# LM13700.net
KiCad netlist of a schematic drawn in EAGLE
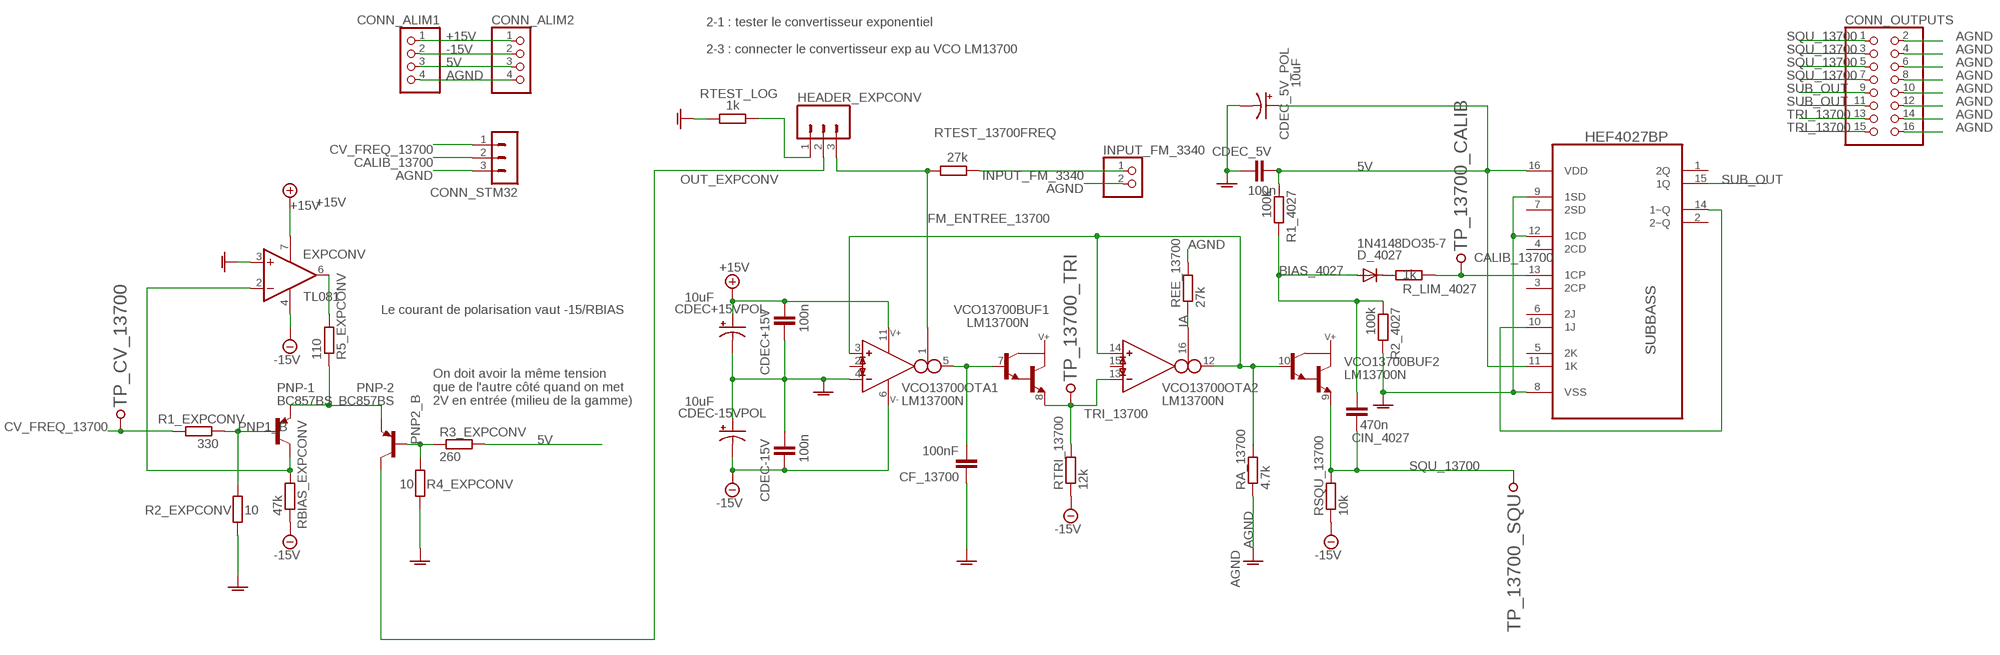
[diagram p0: schematic, sheet 1]

(export (version "E")
  (design (tool "Eeschema 10.0.6"))
  (components
    (comp (ref "CDEC+15V")
      (value "100n")
      (footprint "eagle-import:C025-024X044")
      (libsource (lib "eagle-import") (part "C-EU025-024X044"))
    )
    (comp (ref "CDEC+15VPOL")
      (value "10uF")
      (footprint "eagle-import:CPOL-RADIAL-2.5MM-5MM-KIT")
      (libsource (lib "eagle-import") (part "10UF-POLAR-RADIAL-2.5MM-KIT-25V-20%"))
    )
    (comp (ref "CDEC-15V")
      (value "100n")
      (footprint "eagle-import:C025-024X044")
      (libsource (lib "eagle-import") (part "C-EU025-024X044"))
    )
    (comp (ref "CDEC-15VPOL")
      (value "10uF")
      (footprint "eagle-import:CPOL-RADIAL-2.5MM-5MM-KIT")
      (libsource (lib "eagle-import") (part "10UF-POLAR-RADIAL-2.5MM-KIT-25V-20%"))
    )
    (comp (ref "CDEC_5V")
      (value "100n")
      (footprint "eagle-import:C025-024X044")
      (libsource (lib "eagle-import") (part "C-EU025-024X044"))
    )
    (comp (ref "CDEC_5V_POL")
      (value "10uF")
      (footprint "eagle-import:CPOL-RADIAL-2.5MM-5MM-KIT")
      (libsource (lib "eagle-import") (part "10UF-POLAR-RADIAL-2.5MM-KIT-25V-20%"))
    )
    (comp (ref "CF_13700")
      (value "100nF")
      (footprint "eagle-import:C025-024X044")
      (libsource (lib "eagle-import") (part "C-EU025-024X044"))
    )
    (comp (ref "CIN_4027")
      (value "470n")
      (footprint "eagle-import:C050-024X044")
      (libsource (lib "eagle-import") (part "C-EU050-024X044"))
    )
    (comp (ref "CONN_ALIM1")
      (value "PINHD-1X4")
      (footprint "eagle-import:1X04")
      (libsource (lib "eagle-import") (part "PINHD-1X4"))
    )
    (comp (ref "CONN_ALIM2")
      (value "PINHD-1X4")
      (footprint "eagle-import:1X04")
      (libsource (lib "eagle-import") (part "PINHD-1X4"))
    )
    (comp (ref "CONN_OUTPUTS")
      (value "PINHD-2X8")
      (footprint "eagle-import:2X08")
      (libsource (lib "eagle-import") (part "PINHD-2X8"))
    )
    (comp (ref "CONN_STM32")
      (value "MA03-1")
      (footprint "eagle-import:MA03-1")
      (libsource (lib "eagle-import") (part "MA03-1"))
    )
    (comp (ref "D_4027")
      (value "1N4148DO35-7")
      (footprint "eagle-import:DO35-7")
      (libsource (lib "eagle-import") (part "1N4148DO35-7"))
    )
    (comp (ref "EXPCONV")
      (value "TL081")
      (footprint "eagle-import:DIL08")
      (libsource (lib "eagle-import") (part "1AMP_P7+4N"))
    )
    (comp (ref "HEADER_EXPCONV")
      (value "M03")
      (footprint "eagle-import:03P")
      (libsource (lib "eagle-import") (part "M03"))
    )
    (comp (ref "INPUT_FM_3340")
      (value "PINHD-1X2")
      (footprint "eagle-import:1X02")
      (libsource (lib "eagle-import") (part "PINHD-1X2"))
    )
    (comp (ref "PNP")
      (value "BC857BS")
      (footprint "eagle-import:SOT363")
      (libsource (lib "eagle-import") (part "BC857BS"))
    )
    (comp (ref "R1_4027")
      (value "100k")
      (footprint "eagle-import:0204_5")
      (libsource (lib "eagle-import") (part "R-EU_0204/5"))
    )
    (comp (ref "R1_EXPCONV")
      (value "330")
      (footprint "eagle-import:0204_5")
      (libsource (lib "eagle-import") (part "R-EU_0204/5"))
    )
    (comp (ref "R2_4027")
      (value "100k")
      (footprint "eagle-import:0204_5")
      (libsource (lib "eagle-import") (part "R-EU_0204/5"))
    )
    (comp (ref "R2_EXPCONV")
      (value "10")
      (footprint "eagle-import:0204_5")
      (libsource (lib "eagle-import") (part "R-EU_0204/5"))
    )
    (comp (ref "R3_EXPCONV")
      (value "260")
      (footprint "eagle-import:0204_5")
      (libsource (lib "eagle-import") (part "R-EU_0204/5"))
    )
    (comp (ref "R4_EXPCONV")
      (value "10")
      (footprint "eagle-import:0204_5")
      (libsource (lib "eagle-import") (part "R-EU_0204/5"))
    )
    (comp (ref "R5_EXPCONV")
      (value "110")
      (footprint "eagle-import:0204_5")
      (libsource (lib "eagle-import") (part "R-EU_0204/5"))
    )
    (comp (ref "RA_13700")
      (value "4.7k")
      (footprint "eagle-import:0204_5")
      (libsource (lib "eagle-import") (part "R-EU_0204/5"))
    )
    (comp (ref "RBIAS_EXPCONV")
      (value "47k")
      (footprint "eagle-import:0204_5")
      (libsource (lib "eagle-import") (part "R-EU_0204/5"))
    )
    (comp (ref "REE_13700")
      (value "27k")
      (footprint "eagle-import:0204_5")
      (libsource (lib "eagle-import") (part "R-EU_0204/5"))
    )
    (comp (ref "RSQU_13700")
      (value "10k")
      (footprint "eagle-import:0204_5")
      (libsource (lib "eagle-import") (part "R-EU_0204/5"))
    )
    (comp (ref "RTEST_13700FREQ")
      (value "27k")
      (footprint "eagle-import:0204_5")
      (libsource (lib "eagle-import") (part "R-EU_0204/5"))
    )
    (comp (ref "RTEST_LOG")
      (value "1k")
      (footprint "eagle-import:0204_5")
      (libsource (lib "eagle-import") (part "R-EU_0204/5"))
    )
    (comp (ref "RTRI_13700")
      (value "12k")
      (footprint "eagle-import:0204_5")
      (libsource (lib "eagle-import") (part "R-EU_0204/5"))
    )
    (comp (ref "R_LIM_4027")
      (value "1k")
      (footprint "eagle-import:0204_5")
      (libsource (lib "eagle-import") (part "R-EU_0204/5"))
    )
    (comp (ref "SUBBASS")
      (value "HEF4027BP")
      (footprint "eagle-import:DIP254P762X420-16")
      (fields (field (name "MF") "NXP Semiconductors"))
      (libsource (lib "eagle-import") (part "HEF4027BP"))
    )
    (comp (ref "TP_13700_CALIB")
      (value "TESTPOINT")
      (footprint "eagle-import:TESTPOINT_63")
      (libsource (lib "eagle-import") (part "TESTPOINT"))
    )
    (comp (ref "TP_13700_SQU")
      (value "TESTPOINT")
      (footprint "eagle-import:TESTPOINT_63")
      (libsource (lib "eagle-import") (part "TESTPOINT"))
    )
    (comp (ref "TP_13700_TRI")
      (value "TESTPOINT")
      (footprint "eagle-import:TESTPOINT_63")
      (libsource (lib "eagle-import") (part "TESTPOINT"))
    )
    (comp (ref "TP_CV_13700")
      (value "TESTPOINT")
      (footprint "eagle-import:TESTPOINT_63")
      (libsource (lib "eagle-import") (part "TESTPOINT"))
    )
    (comp (ref "VCO13700")
      (value "LM13700N")
      (footprint "eagle-import:DIL16")
      (libsource (lib "eagle-import") (part "LM13700N"))
    )
  )
  (nets
    (net (code "1") (name "+15V") (class "Default")
      (node (ref "CDEC+15V") (pin "1") (pinfunction "1_1") (pintype "passive"))
      (node (ref "CDEC+15VPOL") (pin "1") (pinfunction "+_1") (pintype "passive"))
      (node (ref "CONN_ALIM1") (pin "1") (pinfunction "1_1") (pintype "passive"))
      (node (ref "CONN_ALIM2") (pin "1") (pinfunction "1_1") (pintype "passive"))
      (node (ref "EXPCONV") (pin "7") (pinfunction "V+_7") (pintype "power_in"))
      (node (ref "VCO13700") (pin "11") (pinfunction "V+_11") (pintype "power_in"))
    )
    (net (code "2") (name "-15V") (class "Default")
      (node (ref "CDEC-15V") (pin "2") (pinfunction "2_2") (pintype "passive"))
      (node (ref "CDEC-15VPOL") (pin "2") (pinfunction "-_2") (pintype "passive"))
      (node (ref "CONN_ALIM1") (pin "2") (pinfunction "2_2") (pintype "passive"))
      (node (ref "CONN_ALIM2") (pin "2") (pinfunction "2_2") (pintype "passive"))
      (node (ref "EXPCONV") (pin "4") (pinfunction "V-_4") (pintype "power_in"))
      (node (ref "RBIAS_EXPCONV") (pin "1") (pinfunction "1_1") (pintype "passive"))
      (node (ref "RSQU_13700") (pin "1") (pinfunction "1_1") (pintype "passive"))
      (node (ref "RTRI_13700") (pin "1") (pinfunction "1_1") (pintype "passive"))
      (node (ref "VCO13700") (pin "6") (pinfunction "V-_6") (pintype "power_in"))
    )
    (net (code "3") (name "/5V") (class "Default")
      (node (ref "CDEC_5V") (pin "1") (pinfunction "1_1") (pintype "passive"))
      (node (ref "CDEC_5V_POL") (pin "1") (pinfunction "+_1") (pintype "passive"))
      (node (ref "CONN_ALIM1") (pin "3") (pinfunction "3_3") (pintype "passive"))
      (node (ref "CONN_ALIM2") (pin "3") (pinfunction "3_3") (pintype "passive"))
      (node (ref "R1_4027") (pin "1") (pinfunction "1_1") (pintype "passive"))
      (node (ref "R3_EXPCONV") (pin "2") (pinfunction "2_2") (pintype "passive"))
      (node (ref "SUBBASS") (pin "11") (pinfunction "1K_11") (pintype "input"))
      (node (ref "SUBBASS") (pin "16") (pinfunction "VDD_16") (pintype "power_in"))
    )
    (net (code "4") (name "/BIAS_4027") (class "Default")
      (node (ref "CIN_4027") (pin "1") (pinfunction "1_1") (pintype "passive"))
      (node (ref "D_4027") (pin "A") (pinfunction "A_A") (pintype "passive"))
      (node (ref "R1_4027") (pin "2") (pinfunction "2_2") (pintype "passive"))
      (node (ref "R2_4027") (pin "1") (pinfunction "1_1") (pintype "passive"))
    )
    (net (code "5") (name "/CALIB_13700") (class "Default")
      (node (ref "CONN_STM32") (pin "2") (pinfunction "2_2") (pintype "passive"))
      (node (ref "R_LIM_4027") (pin "1") (pinfunction "1_1") (pintype "passive"))
      (node (ref "SUBBASS") (pin "13") (pinfunction "1CP_13") (pintype "input"))
      (node (ref "TP_13700_CALIB") (pin "P$1") (pinfunction "P$1_P$1") (pintype "passive"))
    )
    (net (code "6") (name "/CV_FREQ_13700") (class "Default")
      (node (ref "CONN_STM32") (pin "1") (pinfunction "1_1") (pintype "passive"))
      (node (ref "R1_EXPCONV") (pin "2") (pinfunction "2_2") (pintype "passive"))
      (node (ref "TP_CV_13700") (pin "P$1") (pinfunction "P$1_P$1") (pintype "passive"))
    )
    (net (code "7") (name "/FM_ENTREE_13700") (class "Default")
      (node (ref "HEADER_EXPCONV") (pin "3") (pinfunction "3_3") (pintype "passive"))
      (node (ref "RTEST_13700FREQ") (pin "2") (pinfunction "2_2") (pintype "passive"))
      (node (ref "VCO13700") (pin "1") (pinfunction "I_BIAS_1") (pintype "input"))
    )
    (net (code "8") (name "/IA") (class "Default")
      (node (ref "REE_13700") (pin "1") (pinfunction "1_1") (pintype "passive"))
      (node (ref "VCO13700") (pin "16") (pinfunction "I_BIAS_16") (pintype "input"))
    )
    (net (code "9") (name "/INPUT_FM_3340") (class "Default")
      (node (ref "INPUT_FM_3340") (pin "1") (pinfunction "1_1") (pintype "passive"))
      (node (ref "RTEST_13700FREQ") (pin "1") (pinfunction "1_1") (pintype "passive"))
    )
    (net (code "10") (name "/OUT_EXPCONV") (class "Default")
      (node (ref "HEADER_EXPCONV") (pin "2") (pinfunction "2_2") (pintype "passive"))
      (node (ref "PNP") (pin "3") (pinfunction "C_3") (pintype "passive"))
    )
    (net (code "11") (name "/PNP1_B") (class "Default")
      (node (ref "PNP") (pin "2") (pinfunction "B_2") (pintype "passive"))
      (node (ref "R1_EXPCONV") (pin "1") (pinfunction "1_1") (pintype "passive"))
      (node (ref "R2_EXPCONV") (pin "1") (pinfunction "1_1") (pintype "passive"))
    )
    (net (code "12") (name "/PNP2_B") (class "Default")
      (node (ref "PNP") (pin "5") (pinfunction "B_5") (pintype "passive"))
      (node (ref "R3_EXPCONV") (pin "1") (pinfunction "1_1") (pintype "passive"))
      (node (ref "R4_EXPCONV") (pin "1") (pinfunction "1_1") (pintype "passive"))
    )
    (net (code "13") (name "/SQU_13700") (class "Default")
      (node (ref "CIN_4027") (pin "2") (pinfunction "2_2") (pintype "passive"))
      (node (ref "CONN_OUTPUTS") (pin "1") (pinfunction "1_1") (pintype "passive"))
      (node (ref "CONN_OUTPUTS") (pin "3") (pinfunction "3_3") (pintype "passive"))
      (node (ref "CONN_OUTPUTS") (pin "5") (pinfunction "5_5") (pintype "passive"))
      (node (ref "CONN_OUTPUTS") (pin "7") (pinfunction "7_7") (pintype "passive"))
      (node (ref "RSQU_13700") (pin "2") (pinfunction "2_2") (pintype "passive"))
      (node (ref "TP_13700_SQU") (pin "P$1") (pinfunction "P$1_P$1") (pintype "passive"))
      (node (ref "VCO13700") (pin "9") (pinfunction "E_9") (pintype "passive"))
    )
    (net (code "14") (name "/SUB_OUT") (class "Default")
      (node (ref "CONN_OUTPUTS") (pin "11") (pinfunction "11_11") (pintype "passive"))
      (node (ref "CONN_OUTPUTS") (pin "9") (pinfunction "9_9") (pintype "passive"))
      (node (ref "SUBBASS") (pin "15") (pinfunction "1Q_15") (pintype "output"))
    )
    (net (code "15") (name "/TRI_13700") (class "Default")
      (node (ref "CONN_OUTPUTS") (pin "13") (pinfunction "13_13") (pintype "passive"))
      (node (ref "CONN_OUTPUTS") (pin "15") (pinfunction "15_15") (pintype "passive"))
      (node (ref "RTRI_13700") (pin "2") (pinfunction "2_2") (pintype "passive"))
      (node (ref "TP_13700_TRI") (pin "P$1") (pinfunction "P$1_P$1") (pintype "passive"))
      (node (ref "VCO13700") (pin "13") (pinfunction "IN_N_13") (pintype "input"))
      (node (ref "VCO13700") (pin "8") (pinfunction "E_8") (pintype "passive"))
    )
    (net (code "16") (name "AGND") (class "Default")
      (node (ref "CDEC+15V") (pin "2") (pinfunction "2_2") (pintype "passive"))
      (node (ref "CDEC+15VPOL") (pin "2") (pinfunction "-_2") (pintype "passive"))
      (node (ref "CDEC-15V") (pin "1") (pinfunction "1_1") (pintype "passive"))
      (node (ref "CDEC-15VPOL") (pin "1") (pinfunction "+_1") (pintype "passive"))
      (node (ref "CDEC_5V") (pin "2") (pinfunction "2_2") (pintype "passive"))
      (node (ref "CDEC_5V_POL") (pin "2") (pinfunction "-_2") (pintype "passive"))
      (node (ref "CF_13700") (pin "1") (pinfunction "1_1") (pintype "passive"))
      (node (ref "CONN_ALIM1") (pin "4") (pinfunction "4_4") (pintype "passive"))
      (node (ref "CONN_ALIM2") (pin "4") (pinfunction "4_4") (pintype "passive"))
      (node (ref "CONN_OUTPUTS") (pin "10") (pinfunction "10_10") (pintype "passive"))
      (node (ref "CONN_OUTPUTS") (pin "12") (pinfunction "12_12") (pintype "passive"))
      (node (ref "CONN_OUTPUTS") (pin "14") (pinfunction "14_14") (pintype "passive"))
      (node (ref "CONN_OUTPUTS") (pin "16") (pinfunction "16_16") (pintype "passive"))
      (node (ref "CONN_OUTPUTS") (pin "2") (pinfunction "2_2") (pintype "passive"))
      (node (ref "CONN_OUTPUTS") (pin "4") (pinfunction "4_4") (pintype "passive"))
      (node (ref "CONN_OUTPUTS") (pin "6") (pinfunction "6_6") (pintype "passive"))
      (node (ref "CONN_OUTPUTS") (pin "8") (pinfunction "8_8") (pintype "passive"))
      (node (ref "CONN_STM32") (pin "3") (pinfunction "3_3") (pintype "passive"))
      (node (ref "EXPCONV") (pin "3") (pinfunction "+IN_3") (pintype "input"))
      (node (ref "INPUT_FM_3340") (pin "2") (pinfunction "2_2") (pintype "passive"))
      (node (ref "R2_4027") (pin "2") (pinfunction "2_2") (pintype "passive"))
      (node (ref "R2_EXPCONV") (pin "2") (pinfunction "2_2") (pintype "passive"))
      (node (ref "R4_EXPCONV") (pin "2") (pinfunction "2_2") (pintype "passive"))
      (node (ref "RA_13700") (pin "1") (pinfunction "1_1") (pintype "passive"))
      (node (ref "REE_13700") (pin "2") (pinfunction "2_2") (pintype "passive"))
      (node (ref "RTEST_LOG") (pin "2") (pinfunction "2_2") (pintype "passive"))
      (node (ref "SUBBASS") (pin "12") (pinfunction "1CD_12") (pintype "input"))
      (node (ref "SUBBASS") (pin "8") (pinfunction "VSS_8") (pintype "passive"))
      (node (ref "SUBBASS") (pin "9") (pinfunction "1SD_9") (pintype "input"))
      (node (ref "VCO13700") (pin "4") (pinfunction "IN_N_4") (pintype "input"))
    )
    (net (code "17") (name "Net-(D_4027-PadC)") (class "Default")
      (node (ref "D_4027") (pin "C") (pinfunction "C_C") (pintype "passive"))
      (node (ref "R_LIM_4027") (pin "2") (pinfunction "2_2") (pintype "passive"))
    )
    (net (code "18") (name "Net-(EXPCONV--IN)") (class "Default")
      (node (ref "EXPCONV") (pin "2") (pinfunction "-IN_2") (pintype "input"))
      (node (ref "PNP") (pin "6") (pinfunction "C_6") (pintype "passive"))
      (node (ref "RBIAS_EXPCONV") (pin "2") (pinfunction "2_2") (pintype "passive"))
    )
    (net (code "19") (name "Net-(EXPCONV-OUT)") (class "Default")
      (node (ref "EXPCONV") (pin "6") (pinfunction "OUT_6") (pintype "output"))
      (node (ref "R5_EXPCONV") (pin "2") (pinfunction "2_2") (pintype "passive"))
    )
    (net (code "20") (name "Net-(HEADER_EXPCONV-Pad1)") (class "Default")
      (node (ref "HEADER_EXPCONV") (pin "1") (pinfunction "1_1") (pintype "passive"))
      (node (ref "RTEST_LOG") (pin "1") (pinfunction "1_1") (pintype "passive"))
    )
    (net (code "21") (name "Net-(PNPA-E)") (class "Default")
      (node (ref "PNP") (pin "1") (pinfunction "E_1") (pintype "passive"))
      (node (ref "PNP") (pin "4") (pinfunction "E_4") (pintype "passive"))
      (node (ref "R5_EXPCONV") (pin "1") (pinfunction "1_1") (pintype "passive"))
    )
    (net (code "22") (name "Net-(SUBBASS-1J)") (class "Default")
      (node (ref "SUBBASS") (pin "10") (pinfunction "1J_10") (pintype "input"))
      (node (ref "SUBBASS") (pin "14") (pinfunction "1~{Q}_14") (pintype "output"))
    )
    (net (code "23") (name "Net-(VCO13700A-B)") (class "Default")
      (node (ref "CF_13700") (pin "2") (pinfunction "2_2") (pintype "passive"))
      (node (ref "VCO13700") (pin "5") (pinfunction "OUT_5") (pintype "output"))
      (node (ref "VCO13700") (pin "7") (pinfunction "B_7") (pintype "passive"))
    )
    (net (code "24") (name "Net-(VCO13700B-B)") (class "Default")
      (node (ref "RA_13700") (pin "2") (pinfunction "2_2") (pintype "passive"))
      (node (ref "VCO13700") (pin "10") (pinfunction "B_10") (pintype "passive"))
      (node (ref "VCO13700") (pin "12") (pinfunction "OUT_12") (pintype "output"))
      (node (ref "VCO13700") (pin "14") (pinfunction "IN_P_14") (pintype "input"))
      (node (ref "VCO13700") (pin "3") (pinfunction "IN_P_3") (pintype "input"))
    )
    (net (code "25") (name "unconnected-(SUBBASS-2CD-Pad4)") (class "Default")
      (node (ref "SUBBASS") (pin "4") (pinfunction "2CD_4") (pintype "input"))
    )
    (net (code "26") (name "unconnected-(SUBBASS-2CP-Pad3)") (class "Default")
      (node (ref "SUBBASS") (pin "3") (pinfunction "2CP_3") (pintype "input"))
    )
    (net (code "27") (name "unconnected-(SUBBASS-2J-Pad6)") (class "Default")
      (node (ref "SUBBASS") (pin "6") (pinfunction "2J_6") (pintype "input"))
    )
    (net (code "28") (name "unconnected-(SUBBASS-2K-Pad5)") (class "Default")
      (node (ref "SUBBASS") (pin "5") (pinfunction "2K_5") (pintype "input"))
    )
    (net (code "29") (name "unconnected-(SUBBASS-2Q-Pad1)") (class "Default")
      (node (ref "SUBBASS") (pin "1") (pinfunction "2Q_1") (pintype "output"))
    )
    (net (code "30") (name "unconnected-(SUBBASS-2SD-Pad7)") (class "Default")
      (node (ref "SUBBASS") (pin "7") (pinfunction "2SD_7") (pintype "input"))
    )
    (net (code "31") (name "unconnected-(SUBBASS-2~{Q}-Pad2)") (class "Default")
      (node (ref "SUBBASS") (pin "2") (pinfunction "2~{Q}_2") (pintype "output"))
    )
    (net (code "32") (name "unconnected-(VCO13700C-I_DIODE-Pad2)") (class "Default")
      (node (ref "VCO13700") (pin "2") (pinfunction "I_DIODE_2") (pintype "input"))
    )
    (net (code "33") (name "unconnected-(VCO13700D-I_DIODE-Pad15)") (class "Default")
      (node (ref "VCO13700") (pin "15") (pinfunction "I_DIODE_15") (pintype "input"))
    )
  )
)
